# PowerControl.net
KiCad netlist of a schematic drawn in Altium Designer
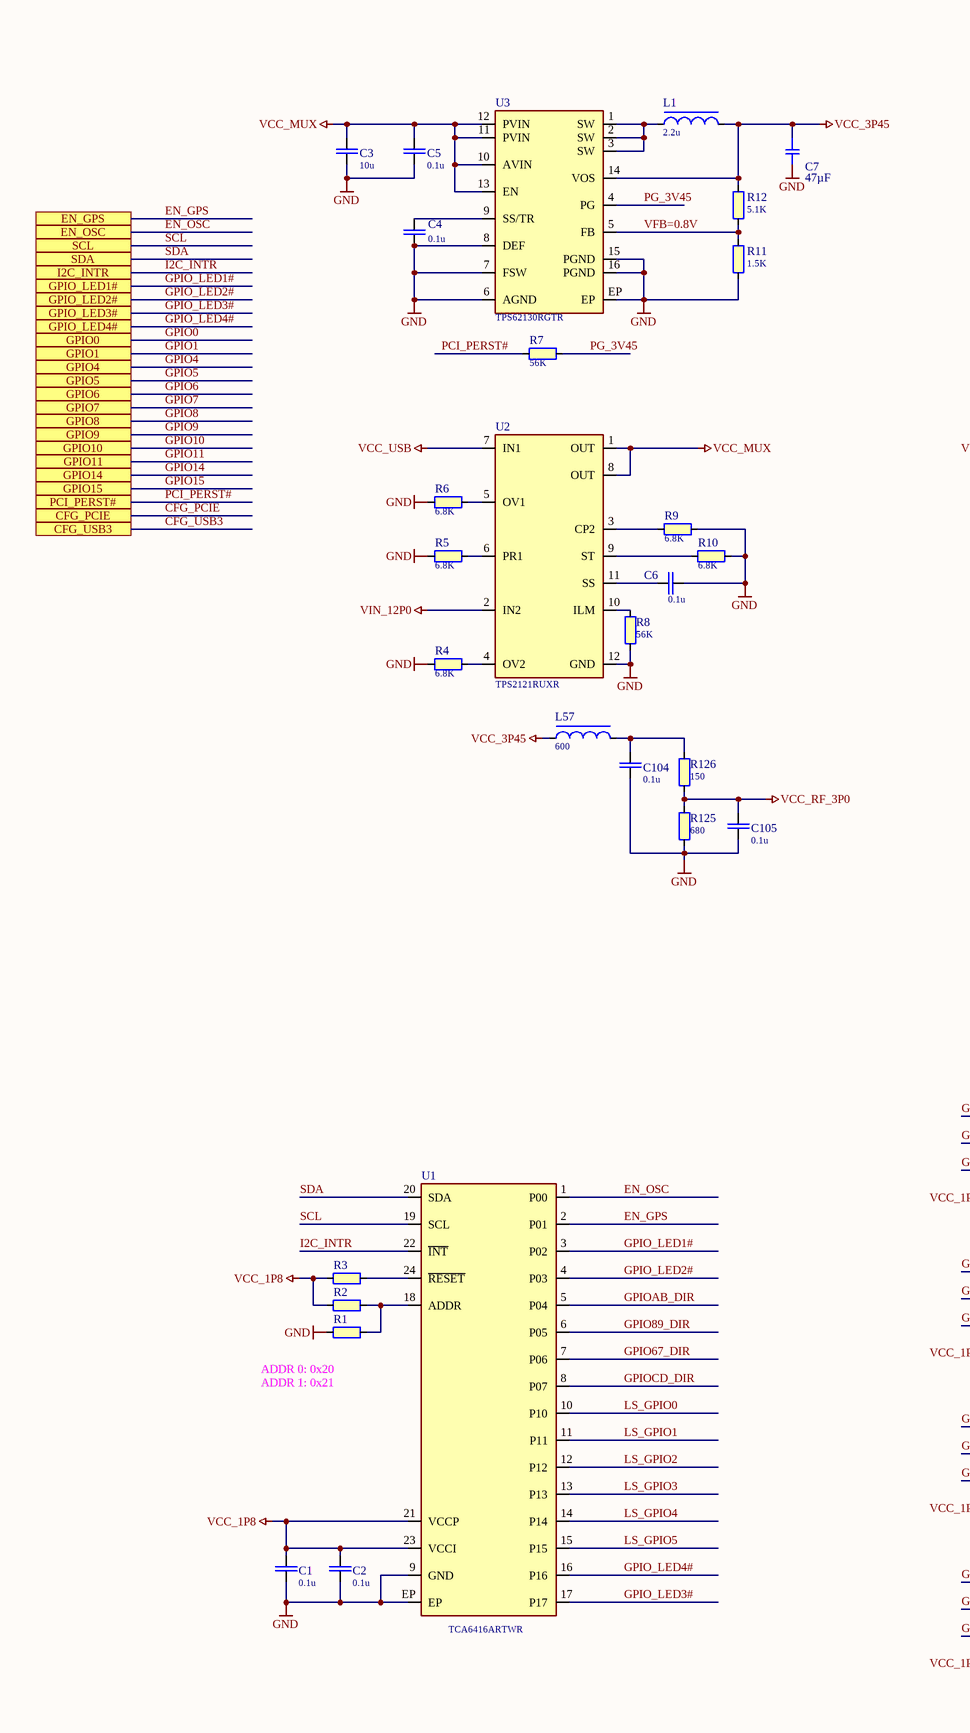
[diagram p0: PowerControl.SchDoc, left]
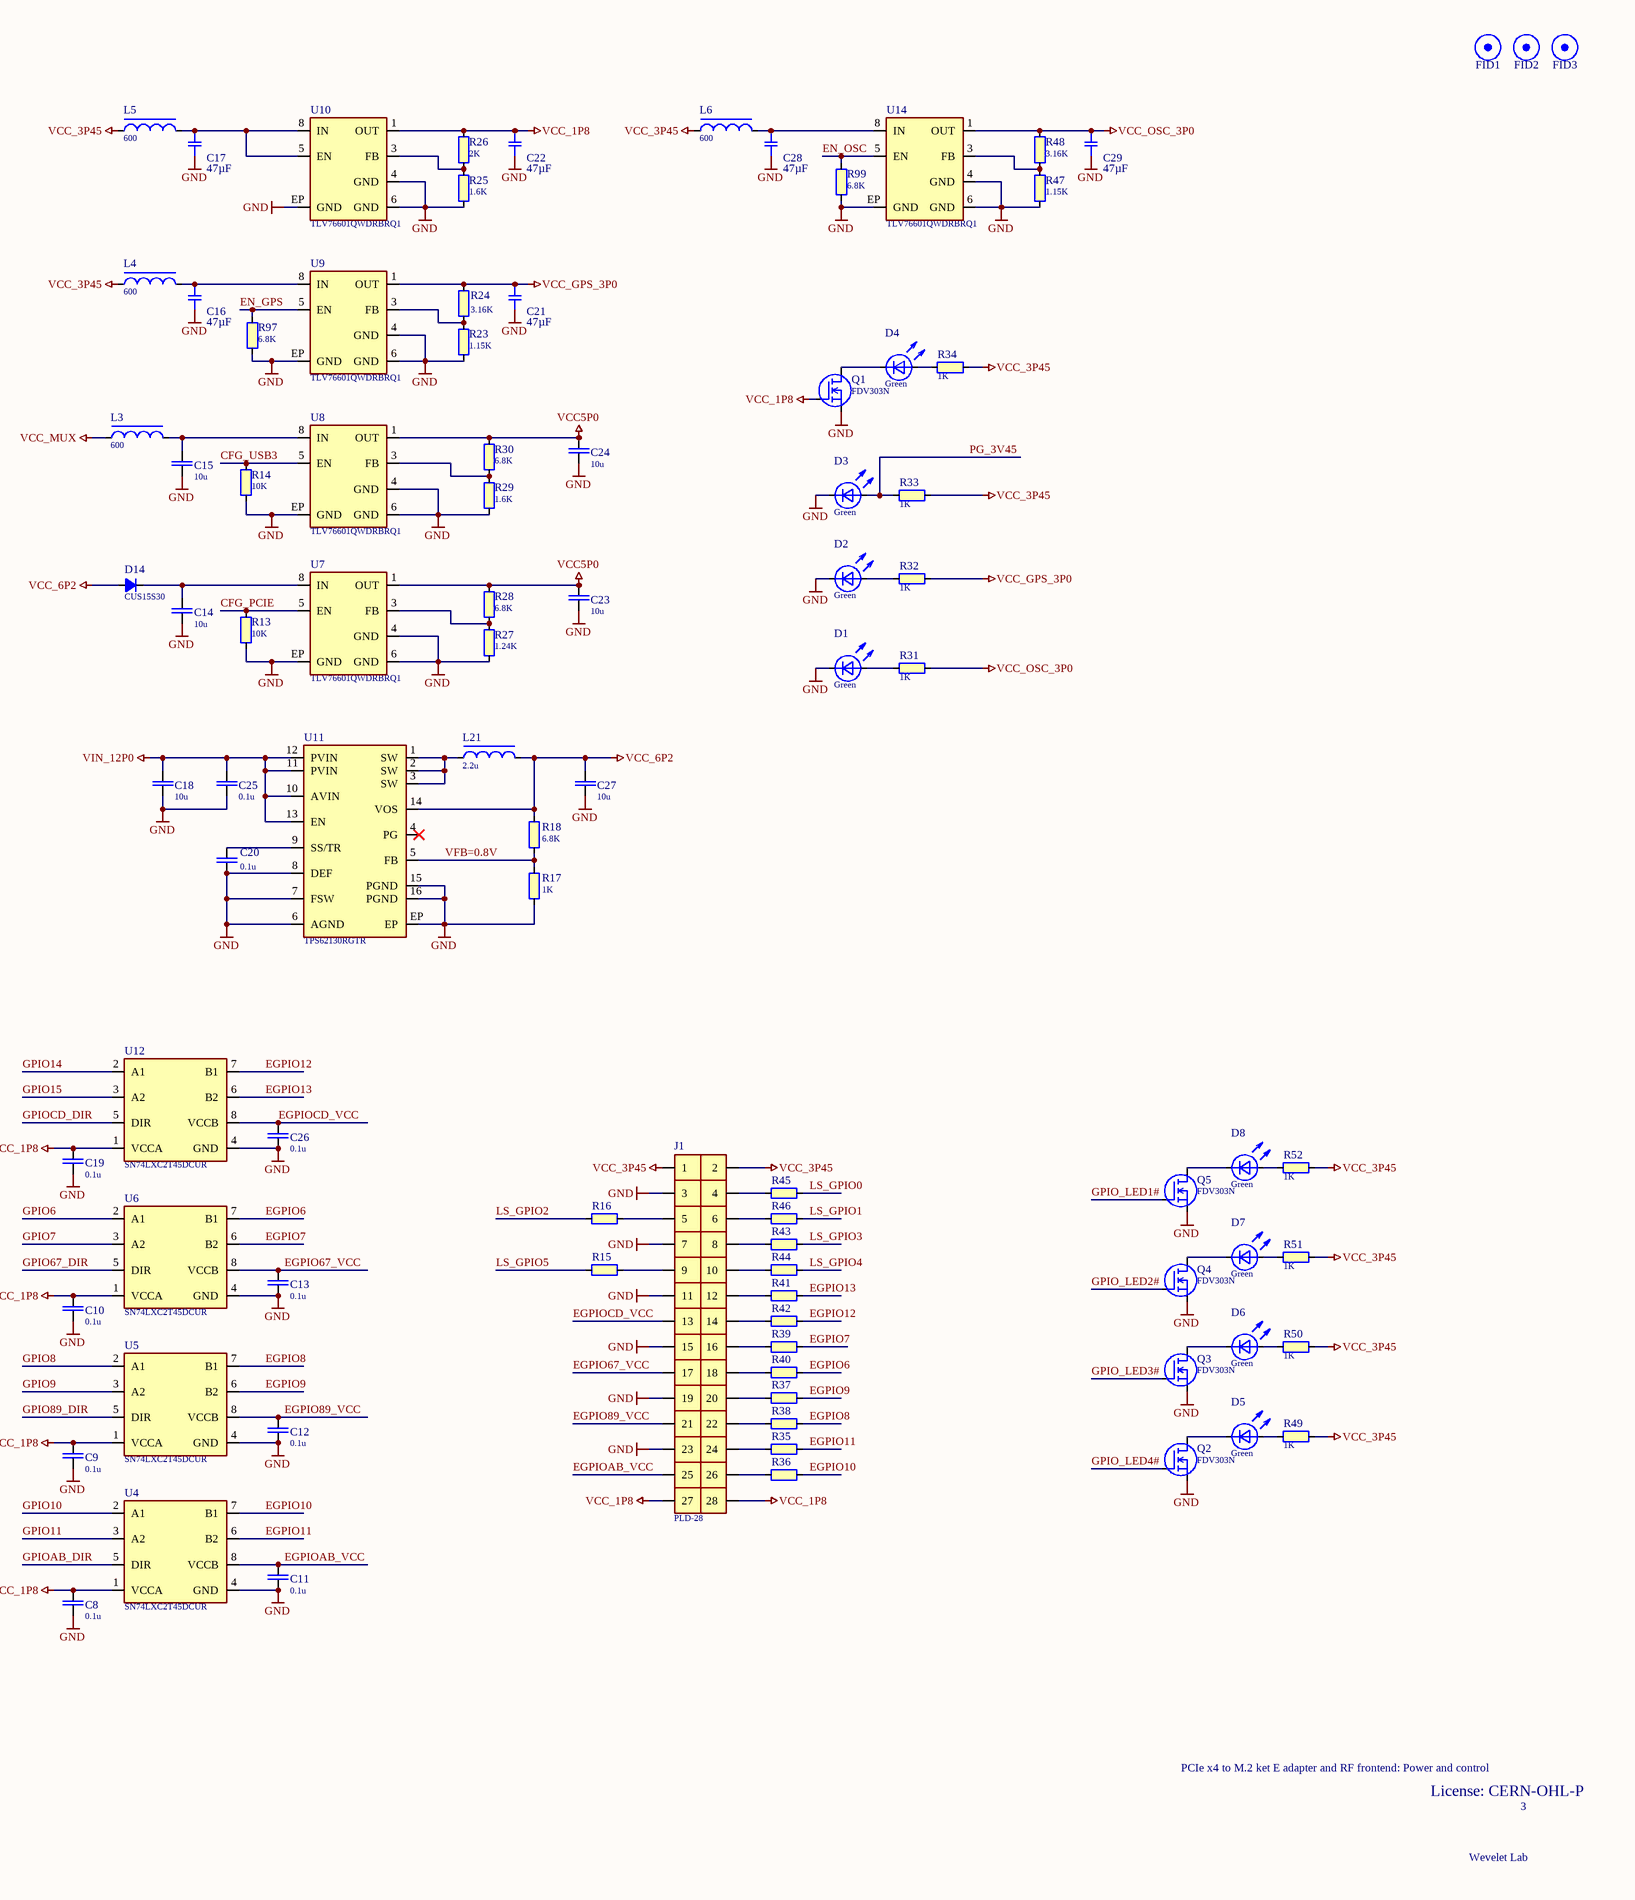
[diagram p1: PowerControl.SchDoc, right]

(export (version "E")
  (design (tool "Eeschema 10.0.6"))
  (components
    (comp (ref "C1")
      (value "0.1u")
      (footprint "CAPC100X50X55L25N")
      (description "Capacitor, 0.1u, 25V, 10%, X7R, 0402")
      (fields
        (field (name "MANUFACTURER") "Murata Electronics")
        (field (name "Comment") "GRM155R71E104KE14D")
      )
      (libsource (lib "Capacitors") (part "GRM155R71E104KE14D"))
    )
    (comp (ref "C2")
      (value "0.1u")
      (footprint "CAPC100X50X55L25N")
      (description "Capacitor, 0.1u, 25V, 10%, X7R, 0402")
      (fields
        (field (name "MANUFACTURER") "Murata Electronics")
        (field (name "Comment") "GRM155R71E104KE14D")
      )
      (libsource (lib "Capacitors") (part "GRM155R71E104KE14D"))
    )
    (comp (ref "C3")
      (value "10u")
      (footprint "CAPC160X80X100L40N")
      (description "Capacitor, 10u, 25V, 20%, X5R, 0603")
      (fields (field (name "Comment") "Cap-0603-X5R-25V-10u-20%"))
      (libsource (lib "Capacitors") (part "Cap-0603-X5R-25V-10u-20%"))
    )
    (comp (ref "C4")
      (value "0.1u")
      (footprint "CAPC100X50X55L25N")
      (description "Capacitor, 0.1u, 25V, 10%, X7R, 0402")
      (fields
        (field (name "MANUFACTURER") "Murata Electronics")
        (field (name "Comment") "GRM155R71E104KE14D")
      )
      (libsource (lib "Capacitors") (part "GRM155R71E104KE14D"))
    )
    (comp (ref "C5")
      (value "0.1u")
      (footprint "CAPC100X50X55L25N")
      (description "Capacitor, 0.1u, 25V, 10%, X7R, 0402")
      (fields
        (field (name "MANUFACTURER") "Murata Electronics")
        (field (name "Comment") "GRM155R71E104KE14D")
      )
      (libsource (lib "Capacitors") (part "GRM155R71E104KE14D"))
    )
    (comp (ref "C6")
      (value "0.1u")
      (footprint "CAPC100X50X55L25N")
      (description "Capacitor, 0.1u, 25V, 10%, X7R, 0402")
      (fields
        (field (name "MANUFACTURER") "Murata Electronics")
        (field (name "Comment") "GRM155R71E104KE14D")
      )
      (libsource (lib "Capacitors") (part "GRM155R71E104KE14D"))
    )
    (comp (ref "C7")
      (value "47µF")
      (footprint "SMD-0603-CAP_HighDensity")
      (description "CAP CER 47UF 4V X6S 0603")
      (fields
        (field (name "MANUFACTURER") "Murata Electronics North America")
        (field (name "DIGI-KEY PART NUMBER") "490-13246-2-ND")
      )
      (libsource (lib "Capacitors") (part "GRM188C80G476ME01D"))
    )
    (comp (ref "C8")
      (value "0.1u")
      (footprint "CAPC100X50X55L25N")
      (description "Capacitor, 0.1u, 25V, 10%, X7R, 0402")
      (fields
        (field (name "MANUFACTURER") "Murata Electronics")
        (field (name "Comment") "GRM155R71E104KE14D")
      )
      (libsource (lib "Capacitors") (part "GRM155R71E104KE14D"))
    )
    (comp (ref "C9")
      (value "0.1u")
      (footprint "CAPC100X50X55L25N")
      (description "Capacitor, 0.1u, 25V, 10%, X7R, 0402")
      (fields
        (field (name "MANUFACTURER") "Murata Electronics")
        (field (name "Comment") "GRM155R71E104KE14D")
      )
      (libsource (lib "Capacitors") (part "GRM155R71E104KE14D"))
    )
    (comp (ref "C10")
      (value "0.1u")
      (footprint "CAPC100X50X55L25N")
      (description "Capacitor, 0.1u, 25V, 10%, X7R, 0402")
      (fields
        (field (name "MANUFACTURER") "Murata Electronics")
        (field (name "Comment") "GRM155R71E104KE14D")
      )
      (libsource (lib "Capacitors") (part "GRM155R71E104KE14D"))
    )
    (comp (ref "C11")
      (value "0.1u")
      (footprint "CAPC100X50X55L25N")
      (description "Capacitor, 0.1u, 25V, 10%, X7R, 0402")
      (fields
        (field (name "MANUFACTURER") "Murata Electronics")
        (field (name "Comment") "GRM155R71E104KE14D")
      )
      (libsource (lib "Capacitors") (part "GRM155R71E104KE14D"))
    )
    (comp (ref "C12")
      (value "0.1u")
      (footprint "CAPC100X50X55L25N")
      (description "Capacitor, 0.1u, 25V, 10%, X7R, 0402")
      (fields
        (field (name "MANUFACTURER") "Murata Electronics")
        (field (name "Comment") "GRM155R71E104KE14D")
      )
      (libsource (lib "Capacitors") (part "GRM155R71E104KE14D"))
    )
    (comp (ref "C13")
      (value "0.1u")
      (footprint "CAPC100X50X55L25N")
      (description "Capacitor, 0.1u, 25V, 10%, X7R, 0402")
      (fields
        (field (name "MANUFACTURER") "Murata Electronics")
        (field (name "Comment") "GRM155R71E104KE14D")
      )
      (libsource (lib "Capacitors") (part "GRM155R71E104KE14D"))
    )
    (comp (ref "C14")
      (value "10u")
      (footprint "CAPC160X80X100L40N")
      (description "Capacitor, 10u, 25V, 20%, X5R, 0603")
      (fields (field (name "Comment") "Cap-0603-X5R-25V-10u-20%"))
      (libsource (lib "Capacitors") (part "Cap-0603-X5R-25V-10u-20%"))
    )
    (comp (ref "C15")
      (value "10u")
      (footprint "CAPC160X80X100L40N")
      (description "Capacitor, 10u, 25V, 20%, X5R, 0603")
      (fields (field (name "Comment") "Cap-0603-X5R-25V-10u-20%"))
      (libsource (lib "Capacitors") (part "Cap-0603-X5R-25V-10u-20%"))
    )
    (comp (ref "C16")
      (value "47µF")
      (footprint "SMD-0603-CAP_HighDensity")
      (description "CAP CER 47UF 4V X6S 0603")
      (fields
        (field (name "MANUFACTURER") "Murata Electronics North America")
        (field (name "DIGI-KEY PART NUMBER") "490-13246-2-ND")
      )
      (libsource (lib "Capacitors") (part "GRM188C80G476ME01D"))
    )
    (comp (ref "C17")
      (value "47µF")
      (footprint "SMD-0603-CAP_HighDensity")
      (description "CAP CER 47UF 4V X6S 0603")
      (fields
        (field (name "MANUFACTURER") "Murata Electronics North America")
        (field (name "DIGI-KEY PART NUMBER") "490-13246-2-ND")
      )
      (libsource (lib "Capacitors") (part "GRM188C80G476ME01D"))
    )
    (comp (ref "C18")
      (value "10u")
      (footprint "CAPC160X80X100L40N")
      (description "Capacitor, 10u, 25V, 20%, X5R, 0603")
      (fields (field (name "Comment") "Cap-0603-X5R-25V-10u-20%"))
      (libsource (lib "Capacitors") (part "Cap-0603-X5R-25V-10u-20%"))
    )
    (comp (ref "C19")
      (value "0.1u")
      (footprint "CAPC100X50X55L25N")
      (description "Capacitor, 0.1u, 25V, 10%, X7R, 0402")
      (fields
        (field (name "MANUFACTURER") "Murata Electronics")
        (field (name "Comment") "GRM155R71E104KE14D")
      )
      (libsource (lib "Capacitors") (part "GRM155R71E104KE14D"))
    )
    (comp (ref "C20")
      (value "0.1u")
      (footprint "CAPC100X50X55L25N")
      (description "Capacitor, 0.1u, 25V, 10%, X7R, 0402")
      (fields
        (field (name "MANUFACTURER") "Murata Electronics")
        (field (name "Comment") "GRM155R71E104KE14D")
      )
      (libsource (lib "Capacitors") (part "GRM155R71E104KE14D"))
    )
    (comp (ref "C21")
      (value "47µF")
      (footprint "SMD-0603-CAP_HighDensity")
      (description "CAP CER 47UF 4V X6S 0603")
      (fields
        (field (name "MANUFACTURER") "Murata Electronics North America")
        (field (name "DIGI-KEY PART NUMBER") "490-13246-2-ND")
      )
      (libsource (lib "Capacitors") (part "GRM188C80G476ME01D"))
    )
    (comp (ref "C22")
      (value "47µF")
      (footprint "SMD-0603-CAP_HighDensity")
      (description "CAP CER 47UF 4V X6S 0603")
      (fields
        (field (name "MANUFACTURER") "Murata Electronics North America")
        (field (name "DIGI-KEY PART NUMBER") "490-13246-2-ND")
      )
      (libsource (lib "Capacitors") (part "GRM188C80G476ME01D"))
    )
    (comp (ref "C23")
      (value "10u")
      (footprint "CAPC160X80X100L40N")
      (description "Capacitor, 10u, 25V, 20%, X5R, 0603")
      (fields (field (name "Comment") "Cap-0603-X5R-25V-10u-20%"))
      (libsource (lib "Capacitors") (part "Cap-0603-X5R-25V-10u-20%"))
    )
    (comp (ref "C24")
      (value "10u")
      (footprint "CAPC160X80X100L40N")
      (description "Capacitor, 10u, 25V, 20%, X5R, 0603")
      (fields (field (name "Comment") "Cap-0603-X5R-25V-10u-20%"))
      (libsource (lib "Capacitors") (part "Cap-0603-X5R-25V-10u-20%"))
    )
    (comp (ref "C25")
      (value "0.1u")
      (footprint "CAPC100X50X55L25N")
      (description "Capacitor, 0.1u, 25V, 10%, X7R, 0402")
      (fields
        (field (name "MANUFACTURER") "Murata Electronics")
        (field (name "Comment") "GRM155R71E104KE14D")
      )
      (libsource (lib "Capacitors") (part "GRM155R71E104KE14D"))
    )
    (comp (ref "C26")
      (value "0.1u")
      (footprint "CAPC100X50X55L25N")
      (description "Capacitor, 0.1u, 25V, 10%, X7R, 0402")
      (fields
        (field (name "MANUFACTURER") "Murata Electronics")
        (field (name "Comment") "GRM155R71E104KE14D")
      )
      (libsource (lib "Capacitors") (part "GRM155R71E104KE14D"))
    )
    (comp (ref "C27")
      (value "10u")
      (footprint "CAPC160X80X100L40N")
      (description "Capacitor, 10u, 25V, 20%, X5R, 0603")
      (fields (field (name "Comment") "Cap-0603-X5R-25V-10u-20%"))
      (libsource (lib "Capacitors") (part "Cap-0603-X5R-25V-10u-20%"))
    )
    (comp (ref "C28")
      (value "47µF")
      (footprint "SMD-0603-CAP_HighDensity")
      (description "CAP CER 47UF 4V X6S 0603")
      (fields
        (field (name "MANUFACTURER") "Murata Electronics North America")
        (field (name "DIGI-KEY PART NUMBER") "490-13246-2-ND")
      )
      (libsource (lib "Capacitors") (part "GRM188C80G476ME01D"))
    )
    (comp (ref "C29")
      (value "47µF")
      (footprint "SMD-0603-CAP_HighDensity")
      (description "CAP CER 47UF 4V X6S 0603")
      (fields
        (field (name "MANUFACTURER") "Murata Electronics North America")
        (field (name "DIGI-KEY PART NUMBER") "490-13246-2-ND")
      )
      (libsource (lib "Capacitors") (part "GRM188C80G476ME01D"))
    )
    (comp (ref "C104")
      (value "0.1u")
      (footprint "CAPC100X50X55L25N")
      (description "Capacitor, 0.1u, 25V, 10%, X7R, 0402")
      (fields
        (field (name "MANUFACTURER") "Murata Electronics")
        (field (name "Comment") "GRM155R71E104KE14D")
      )
      (libsource (lib "Capacitors") (part "GRM155R71E104KE14D"))
    )
    (comp (ref "C105")
      (value "0.1u")
      (footprint "CAPC100X50X55L25N")
      (description "Capacitor, 0.1u, 25V, 10%, X7R, 0402")
      (fields
        (field (name "MANUFACTURER") "Murata Electronics")
        (field (name "Comment") "GRM155R71E104KE14D")
      )
      (libsource (lib "Capacitors") (part "GRM155R71E104KE14D"))
    )
    (comp (ref "D1")
      (value "Green")
      (footprint "LEDC160X80X80L40N-Green")
      (description "LED Diode, Green, -30/+85, SMD0603")
      (fields (field (name "MANUFACTURER") "Lite-On Inc.") (field (name "Comment") "LTST-C190KGKT"))
      (libsource (lib "Diode_Transistor") (part "LTST-C190KGKT"))
    )
    (comp (ref "D2")
      (value "Green")
      (footprint "LEDC160X80X80L40N-Green")
      (description "LED Diode, Green, -30/+85, SMD0603")
      (fields (field (name "MANUFACTURER") "Lite-On Inc.") (field (name "Comment") "LTST-C190KGKT"))
      (libsource (lib "Diode_Transistor") (part "LTST-C190KGKT"))
    )
    (comp (ref "D3")
      (value "Green")
      (footprint "LEDC160X80X80L40N-Green")
      (description "LED Diode, Green, -30/+85, SMD0603")
      (fields (field (name "MANUFACTURER") "Lite-On Inc.") (field (name "Comment") "LTST-C190KGKT"))
      (libsource (lib "Diode_Transistor") (part "LTST-C190KGKT"))
    )
    (comp (ref "D4")
      (value "Green")
      (footprint "LEDC160X80X80L40N-Green")
      (description "LED Diode, Green, -30/+85, SMD0603")
      (fields (field (name "MANUFACTURER") "Lite-On Inc.") (field (name "Comment") "LTST-C190KGKT"))
      (libsource (lib "Diode_Transistor") (part "LTST-C190KGKT"))
    )
    (comp (ref "D5")
      (value "Green")
      (footprint "LEDC160X80X80L40N-Green")
      (description "LED Diode, Green, -30/+85, SMD0603")
      (fields (field (name "MANUFACTURER") "Lite-On Inc.") (field (name "Comment") "LTST-C190KGKT"))
      (libsource (lib "Diode_Transistor") (part "LTST-C190KGKT"))
    )
    (comp (ref "D6")
      (value "Green")
      (footprint "LEDC160X80X80L40N-Green")
      (description "LED Diode, Green, -30/+85, SMD0603")
      (fields (field (name "MANUFACTURER") "Lite-On Inc.") (field (name "Comment") "LTST-C190KGKT"))
      (libsource (lib "Diode_Transistor") (part "LTST-C190KGKT"))
    )
    (comp (ref "D7")
      (value "Green")
      (footprint "LEDC160X80X80L40N-Green")
      (description "LED Diode, Green, -30/+85, SMD0603")
      (fields (field (name "MANUFACTURER") "Lite-On Inc.") (field (name "Comment") "LTST-C190KGKT"))
      (libsource (lib "Diode_Transistor") (part "LTST-C190KGKT"))
    )
    (comp (ref "D8")
      (value "Green")
      (footprint "LEDC160X80X80L40N-Green")
      (description "LED Diode, Green, -30/+85, SMD0603")
      (fields (field (name "MANUFACTURER") "Lite-On Inc.") (field (name "Comment") "LTST-C190KGKT"))
      (libsource (lib "Diode_Transistor") (part "LTST-C190KGKT"))
    )
    (comp (ref "D14")
      (value "CUS15S30")
      (footprint "INDC100X60X60L30N")
      (description "Diode, Schottky, 20V, 1.5A, 0.3Vf, -50/+125, SOD-323-2")
      (fields (field (name "MANUFACTURER") "Toshiba") (field (name "Comment") "CUS15S30,H3F"))
      (libsource (lib "Diode_Transistor") (part "CUS15S30"))
    )
    (comp (ref "FID1")
      (value "Fiducial")
      (footprint "Fiducial_3D")
      (libsource (lib "Mech") (part "Fiducial"))
    )
    (comp (ref "FID2")
      (value "Fiducial")
      (footprint "Fiducial_3D")
      (libsource (lib "Mech") (part "Fiducial"))
    )
    (comp (ref "FID3")
      (value "Fiducial")
      (footprint "Fiducial_3D")
      (libsource (lib "Mech") (part "Fiducial"))
    )
    (comp (ref "J1")
      (value "PLD-28")
      (footprint "PLD-28")
      (description "Conn, Header 12x2, 2.54mm, Trough Hole")
      (libsource (lib "Connectors") (part "PLD-28"))
    )
    (comp (ref "L1")
      (value "2.2u")
      (footprint "IND_TAIYO_NRS5020")
      (description "Inductor, 2.2u, 2,9A, 42mOhm, +/-30%, -25/+125, SMD")
      (fields (field (name "MANUFACTURER") "Taiyo Yuden") (field (name "Comment") "NRS5020T2R2NMGJ"))
      (libsource (lib "Inductor_Transformer") (part "NRS5020T2R2NMGJ"))
    )
    (comp (ref "L3")
      (value "600")
      (footprint "INDC100X60X60L30N")
      (description "Ferrite bead, 600Ohm@100MHz, 0,3A, 700mOhm, -55/+125, SMD0402")
      (fields (field (name "MANUFACTURER") "Murata Electronics") (field (name "Comment") "BLM15HG601SN1D"))
      (libsource (lib "Inductor_Transformer") (part "BLM15HG601SN1D"))
    )
    (comp (ref "L4")
      (value "600")
      (footprint "INDC100X60X60L30N")
      (description "Ferrite bead, 600Ohm@100MHz, 0,3A, 700mOhm, -55/+125, SMD0402")
      (fields (field (name "MANUFACTURER") "Murata Electronics") (field (name "Comment") "BLM15HG601SN1D"))
      (libsource (lib "Inductor_Transformer") (part "BLM15HG601SN1D"))
    )
    (comp (ref "L5")
      (value "600")
      (footprint "INDC100X60X60L30N")
      (description "Ferrite bead, 600Ohm@100MHz, 0,3A, 700mOhm, -55/+125, SMD0402")
      (fields (field (name "MANUFACTURER") "Murata Electronics") (field (name "Comment") "BLM15HG601SN1D"))
      (libsource (lib "Inductor_Transformer") (part "BLM15HG601SN1D"))
    )
    (comp (ref "L6")
      (value "600")
      (footprint "INDC100X60X60L30N")
      (description "Ferrite bead, 600Ohm@100MHz, 0,3A, 700mOhm, -55/+125, SMD0402")
      (fields (field (name "MANUFACTURER") "Murata Electronics") (field (name "Comment") "BLM15HG601SN1D"))
      (libsource (lib "Inductor_Transformer") (part "BLM15HG601SN1D"))
    )
    (comp (ref "L21")
      (value "2.2u")
      (footprint "IND_TAIYO_NRS5020")
      (description "Inductor, 2.2u, 2,9A, 42mOhm, +/-30%, -25/+125, SMD")
      (fields (field (name "MANUFACTURER") "Taiyo Yuden") (field (name "Comment") "NRS5020T2R2NMGJ"))
      (libsource (lib "Inductor_Transformer") (part "NRS5020T2R2NMGJ"))
    )
    (comp (ref "L57")
      (value "600")
      (footprint "INDC100X60X60L30N")
      (description "Ferrite bead, 600Ohm@100MHz, 0,3A, 700mOhm, -55/+125, SMD0402")
      (fields (field (name "MANUFACTURER") "Murata Electronics") (field (name "Comment") "BLM15HG601SN1D"))
      (libsource (lib "Inductor_Transformer") (part "BLM15HG601SN1D"))
    )
    (comp (ref "Q1")
      (value "FDV303N")
      (footprint "SOT23-3P95_245X110L45X44N")
      (description "Transistor, MOSFET, N-CH, 25V, 0.68A, -55/+150, SOT-23")
      (fields (field (name "MANUFACTURER") "Onsemi"))
      (libsource (lib "Diode_Transistor") (part "FDV303N"))
    )
    (comp (ref "Q2")
      (value "FDV303N")
      (footprint "SOT23-3P95_245X110L45X44N")
      (description "Transistor, MOSFET, N-CH, 25V, 0.68A, -55/+150, SOT-23")
      (fields (field (name "MANUFACTURER") "Onsemi"))
      (libsource (lib "Diode_Transistor") (part "FDV303N"))
    )
    (comp (ref "Q3")
      (value "FDV303N")
      (footprint "SOT23-3P95_245X110L45X44N")
      (description "Transistor, MOSFET, N-CH, 25V, 0.68A, -55/+150, SOT-23")
      (fields (field (name "MANUFACTURER") "Onsemi"))
      (libsource (lib "Diode_Transistor") (part "FDV303N"))
    )
    (comp (ref "Q4")
      (value "FDV303N")
      (footprint "SOT23-3P95_245X110L45X44N")
      (description "Transistor, MOSFET, N-CH, 25V, 0.68A, -55/+150, SOT-23")
      (fields (field (name "MANUFACTURER") "Onsemi"))
      (libsource (lib "Diode_Transistor") (part "FDV303N"))
    )
    (comp (ref "Q5")
      (value "FDV303N")
      (footprint "SOT23-3P95_245X110L45X44N")
      (description "Transistor, MOSFET, N-CH, 25V, 0.68A, -55/+150, SOT-23")
      (fields (field (name "MANUFACTURER") "Onsemi"))
      (libsource (lib "Diode_Transistor") (part "FDV303N"))
    )
    (comp (ref "R1")
      (value "DNP")
      (footprint "RESC100X50X40L20N")
      (description "Resistor, DNP, 0.063W, 5%, 0402")
      (fields (field (name "Comment") "Res-0402-DNP"))
      (libsource (lib "Resistors") (part "Res-0402-DNP"))
    )
    (comp (ref "R2")
      (value "33")
      (footprint "RESC100X50X40L20N")
      (description "Resistor, 33, 0.063W, 5%, 0402")
      (fields (field (name "Comment") "RC0402FR-0733RL"))
      (libsource (lib "Resistors") (part "Res-0402-33-5%"))
    )
    (comp (ref "R3")
      (value "6.8K")
      (footprint "RESC100X50X40L20N")
      (description "Resistor, 6.8K, 0.063W, 1%, 0402")
      (fields (field (name "Comment") "RC0402FR-076K8L"))
      (libsource (lib "Resistors") (part "Res-0402-6.8K-1%"))
    )
    (comp (ref "R4")
      (value "6.8K")
      (footprint "RESC100X50X40L20N")
      (description "Resistor, 6.8K, 0.063W, 1%, 0402")
      (fields (field (name "Comment") "RC0402FR-076K8L"))
      (libsource (lib "Resistors") (part "Res-0402-6.8K-1%"))
    )
    (comp (ref "R5")
      (value "6.8K")
      (footprint "RESC100X50X40L20N")
      (description "Resistor, 6.8K, 0.063W, 1%, 0402")
      (fields (field (name "Comment") "RC0402FR-076K8L"))
      (libsource (lib "Resistors") (part "Res-0402-6.8K-1%"))
    )
    (comp (ref "R6")
      (value "6.8K")
      (footprint "RESC100X50X40L20N")
      (description "Resistor, 6.8K, 0.063W, 1%, 0402")
      (fields (field (name "Comment") "RC0402FR-076K8L"))
      (libsource (lib "Resistors") (part "Res-0402-6.8K-1%"))
    )
    (comp (ref "R7")
      (value "56K")
      (footprint "RESC100X50X40L20N")
      (description "Resistor, 56K, 0.063W, 5%, 0402")
      (fields (field (name "Comment") "RC0402FR-0756KL"))
      (libsource (lib "Resistors") (part "Res-0402-56K-5%"))
    )
    (comp (ref "R8")
      (value "56K")
      (footprint "RESC100X50X40L20N")
      (description "Resistor, 56K, 0.063W, 5%, 0402")
      (fields (field (name "Comment") "RC0402FR-0756KL"))
      (libsource (lib "") (part "Res-0402-56K-5%_1"))
    )
    (comp (ref "R9")
      (value "6.8K")
      (footprint "RESC100X50X40L20N")
      (description "Resistor, 6.8K, 0.063W, 1%, 0402")
      (fields (field (name "Comment") "RC0402FR-076K8L"))
      (libsource (lib "Resistors") (part "Res-0402-6.8K-1%"))
    )
    (comp (ref "R10")
      (value "6.8K")
      (footprint "RESC100X50X40L20N")
      (description "Resistor, 6.8K, 0.063W, 1%, 0402")
      (fields (field (name "Comment") "RC0402FR-076K8L"))
      (libsource (lib "Resistors") (part "Res-0402-6.8K-1%"))
    )
    (comp (ref "R11")
      (value "1.5K")
      (footprint "RESC100X50X40L20N")
      (description "Resistor, 1.5K, 0.063W, 1%, 0402")
      (fields (field (name "Comment") "RC0402FR-071K5L"))
      (libsource (lib "Resistors") (part "Res-0402-1.5K-1%"))
    )
    (comp (ref "R12")
      (value "5.1K")
      (footprint "RESC100X50X40L20N")
      (description "Resistor, 5.1K, 0.063W, 1%, 0402")
      (fields (field (name "Comment") "RC0402FR-075K1L"))
      (libsource (lib "Resistors") (part "Res-0402-5.1K-1%"))
    )
    (comp (ref "R13")
      (value "10K")
      (footprint "RESC100X50X40L20N")
      (description "Resistor, 10K, 0.063W, 5%, 0402")
      (fields (field (name "Comment") "RC0402FR-0710KL"))
      (libsource (lib "Resistors") (part "Res-0402-10K-5%"))
    )
    (comp (ref "R14")
      (value "10K")
      (footprint "RESC100X50X40L20N")
      (description "Resistor, 10K, 0.063W, 5%, 0402")
      (fields (field (name "Comment") "RC0402FR-0710KL"))
      (libsource (lib "Resistors") (part "Res-0402-10K-5%"))
    )
    (comp (ref "R15")
      (value "33")
      (footprint "RESC100X50X40L20N")
      (description "Resistor, 33, 0.063W, 5%, 0402")
      (fields (field (name "Comment") "RC0402FR-0733RL"))
      (libsource (lib "Resistors") (part "Res-0402-33-5%"))
    )
    (comp (ref "R16")
      (value "33")
      (footprint "RESC100X50X40L20N")
      (description "Resistor, 33, 0.063W, 5%, 0402")
      (fields (field (name "Comment") "RC0402FR-0733RL"))
      (libsource (lib "Resistors") (part "Res-0402-33-5%"))
    )
    (comp (ref "R17")
      (value "1K")
      (footprint "RESC100X50X40L20N")
      (description "Resistor, 1K, 0.063W, 5%, 0402")
      (fields (field (name "Comment") "RC0402FR-071KL"))
      (libsource (lib "") (part "Res-0402-1K-5%_1"))
    )
    (comp (ref "R18")
      (value "6.8K")
      (footprint "RESC100X50X40L20N")
      (description "Resistor, 6.8K, 0.063W, 1%, 0402")
      (fields (field (name "Comment") "RC0402FR-076K8L"))
      (libsource (lib "") (part "Res-0402-6.8K-1%_1"))
    )
    (comp (ref "R23")
      (value "1.15K")
      (footprint "RESC100X50X40L20N")
      (description "Resistor, 1.15K, 0.063W, 1%, 0402")
      (fields (field (name "Comment") "RC0402FR-071K15L"))
      (libsource (lib "Resistors") (part "Res-0402-1.15K-1%"))
    )
    (comp (ref "R24")
      (value "3.16K")
      (footprint "RESC100X50X40L20N")
      (description "Resistor, 3.16K, 0.063W, 1%, 0402")
      (fields (field (name "Comment") "RC0402FR-073K16L"))
      (libsource (lib "Resistors") (part "Res-0402-3.16K-1%"))
    )
    (comp (ref "R25")
      (value "1.6K")
      (footprint "RESC100X50X40L20N")
      (description "Resistor, 1.6K, 0.063W, 1%, 0402")
      (fields (field (name "Comment") "RC0402FR-071K6L"))
      (libsource (lib "Resistors") (part "Res-0402-1.6K-1%"))
    )
    (comp (ref "R26")
      (value "2K")
      (footprint "RESC100X50X40L20N")
      (description "Resistor, 2K, 0.063W, 1%, 0402")
      (fields (field (name "Comment") "RC0402FR-072KL"))
      (libsource (lib "Resistors") (part "Res-0402-2K-1%"))
    )
    (comp (ref "R27")
      (value "1.24K")
      (footprint "RESC100X50X40L20N")
      (description "Resistor, 1.24K, 0.063W, 1%, 0402")
      (fields (field (name "Comment") "RC0402FR-071K24L"))
      (libsource (lib "Resistors") (part "Res-0402-1.24K-1%"))
    )
    (comp (ref "R28")
      (value "6.8K")
      (footprint "RESC100X50X40L20N")
      (description "Resistor, 6.8K, 0.063W, 1%, 0402")
      (fields (field (name "Comment") "RC0402FR-076K8L"))
      (libsource (lib "") (part "Res-0402-6.8K-1%_1"))
    )
    (comp (ref "R29")
      (value "1.6K")
      (footprint "RESC100X50X40L20N")
      (description "Resistor, 1.6K, 0.063W, 1%, 0402")
      (fields (field (name "Comment") "RC0402FR-071K6L"))
      (libsource (lib "Resistors") (part "Res-0402-1.6K-1%"))
    )
    (comp (ref "R30")
      (value "6.8K")
      (footprint "RESC100X50X40L20N")
      (description "Resistor, 6.8K, 0.063W, 1%, 0402")
      (fields (field (name "Comment") "RC0402FR-076K8L"))
      (libsource (lib "") (part "Res-0402-6.8K-1%_1"))
    )
    (comp (ref "R31")
      (value "1K")
      (footprint "RESC100X50X40L20N")
      (description "Resistor, 1K, 0.063W, 5%, 0402")
      (fields (field (name "Comment") "RC0402FR-071KL"))
      (libsource (lib "Resistors") (part "Res-0402-1K-5%"))
    )
    (comp (ref "R32")
      (value "1K")
      (footprint "RESC100X50X40L20N")
      (description "Resistor, 1K, 0.063W, 5%, 0402")
      (fields (field (name "Comment") "RC0402FR-071KL"))
      (libsource (lib "Resistors") (part "Res-0402-1K-5%"))
    )
    (comp (ref "R33")
      (value "1K")
      (footprint "RESC100X50X40L20N")
      (description "Resistor, 1K, 0.063W, 5%, 0402")
      (fields (field (name "Comment") "RC0402FR-071KL"))
      (libsource (lib "Resistors") (part "Res-0402-1K-5%"))
    )
    (comp (ref "R34")
      (value "1K")
      (footprint "RESC100X50X40L20N")
      (description "Resistor, 1K, 0.063W, 5%, 0402")
      (fields (field (name "Comment") "RC0402FR-071KL"))
      (libsource (lib "Resistors") (part "Res-0402-1K-5%"))
    )
    (comp (ref "R35")
      (value "33")
      (footprint "RESC100X50X40L20N")
      (description "Resistor, 33, 0.063W, 5%, 0402")
      (fields (field (name "Comment") "RC0402FR-0733RL"))
      (libsource (lib "Resistors") (part "Res-0402-33-5%"))
    )
    (comp (ref "R36")
      (value "33")
      (footprint "RESC100X50X40L20N")
      (description "Resistor, 33, 0.063W, 5%, 0402")
      (fields (field (name "Comment") "RC0402FR-0733RL"))
      (libsource (lib "Resistors") (part "Res-0402-33-5%"))
    )
    (comp (ref "R37")
      (value "33")
      (footprint "RESC100X50X40L20N")
      (description "Resistor, 33, 0.063W, 5%, 0402")
      (fields (field (name "Comment") "RC0402FR-0733RL"))
      (libsource (lib "Resistors") (part "Res-0402-33-5%"))
    )
    (comp (ref "R38")
      (value "33")
      (footprint "RESC100X50X40L20N")
      (description "Resistor, 33, 0.063W, 5%, 0402")
      (fields (field (name "Comment") "RC0402FR-0733RL"))
      (libsource (lib "Resistors") (part "Res-0402-33-5%"))
    )
    (comp (ref "R39")
      (value "33")
      (footprint "RESC100X50X40L20N")
      (description "Resistor, 33, 0.063W, 5%, 0402")
      (fields (field (name "Comment") "RC0402FR-0733RL"))
      (libsource (lib "Resistors") (part "Res-0402-33-5%"))
    )
    (comp (ref "R40")
      (value "33")
      (footprint "RESC100X50X40L20N")
      (description "Resistor, 33, 0.063W, 5%, 0402")
      (fields (field (name "Comment") "RC0402FR-0733RL"))
      (libsource (lib "Resistors") (part "Res-0402-33-5%"))
    )
    (comp (ref "R41")
      (value "33")
      (footprint "RESC100X50X40L20N")
      (description "Resistor, 33, 0.063W, 5%, 0402")
      (fields (field (name "Comment") "RC0402FR-0733RL"))
      (libsource (lib "Resistors") (part "Res-0402-33-5%"))
    )
    (comp (ref "R42")
      (value "33")
      (footprint "RESC100X50X40L20N")
      (description "Resistor, 33, 0.063W, 5%, 0402")
      (fields (field (name "Comment") "RC0402FR-0733RL"))
      (libsource (lib "Resistors") (part "Res-0402-33-5%"))
    )
    (comp (ref "R43")
      (value "33")
      (footprint "RESC100X50X40L20N")
      (description "Resistor, 33, 0.063W, 5%, 0402")
      (fields (field (name "Comment") "RC0402FR-0733RL"))
      (libsource (lib "Resistors") (part "Res-0402-33-5%"))
    )
    (comp (ref "R44")
      (value "33")
      (footprint "RESC100X50X40L20N")
      (description "Resistor, 33, 0.063W, 5%, 0402")
      (fields (field (name "Comment") "RC0402FR-0733RL"))
      (libsource (lib "Resistors") (part "Res-0402-33-5%"))
    )
    (comp (ref "R45")
      (value "33")
      (footprint "RESC100X50X40L20N")
      (description "Resistor, 33, 0.063W, 5%, 0402")
      (fields (field (name "Comment") "RC0402FR-0733RL"))
      (libsource (lib "Resistors") (part "Res-0402-33-5%"))
    )
    (comp (ref "R46")
      (value "33")
      (footprint "RESC100X50X40L20N")
      (description "Resistor, 33, 0.063W, 5%, 0402")
      (fields (field (name "Comment") "RC0402FR-0733RL"))
      (libsource (lib "Resistors") (part "Res-0402-33-5%"))
    )
    (comp (ref "R47")
      (value "1.15K")
      (footprint "RESC100X50X40L20N")
      (description "Resistor, 1.15K, 0.063W, 1%, 0402")
      (fields (field (name "Comment") "RC0402FR-071K15L"))
      (libsource (lib "Resistors") (part "Res-0402-1.15K-1%"))
    )
    (comp (ref "R48")
      (value "3.16K")
      (footprint "RESC100X50X40L20N")
      (description "Resistor, 3.16K, 0.063W, 1%, 0402")
      (fields (field (name "Comment") "RC0402FR-073K16L"))
      (libsource (lib "Resistors") (part "Res-0402-3.16K-1%"))
    )
    (comp (ref "R49")
      (value "1K")
      (footprint "RESC100X50X40L20N")
      (description "Resistor, 1K, 0.063W, 5%, 0402")
      (fields (field (name "Comment") "RC0402FR-071KL"))
      (libsource (lib "Resistors") (part "Res-0402-1K-5%"))
    )
    (comp (ref "R50")
      (value "1K")
      (footprint "RESC100X50X40L20N")
      (description "Resistor, 1K, 0.063W, 5%, 0402")
      (fields (field (name "Comment") "RC0402FR-071KL"))
      (libsource (lib "Resistors") (part "Res-0402-1K-5%"))
    )
    (comp (ref "R51")
      (value "1K")
      (footprint "RESC100X50X40L20N")
      (description "Resistor, 1K, 0.063W, 5%, 0402")
      (fields (field (name "Comment") "RC0402FR-071KL"))
      (libsource (lib "Resistors") (part "Res-0402-1K-5%"))
    )
    (comp (ref "R52")
      (value "1K")
      (footprint "RESC100X50X40L20N")
      (description "Resistor, 1K, 0.063W, 5%, 0402")
      (fields (field (name "Comment") "RC0402FR-071KL"))
      (libsource (lib "Resistors") (part "Res-0402-1K-5%"))
    )
    (comp (ref "R97")
      (value "6.8K")
      (footprint "RESC100X50X40L20N")
      (description "Resistor, 6.8K, 0.063W, 1%, 0402")
      (fields (field (name "Comment") "RC0402FR-076K8L"))
      (libsource (lib "") (part "Res-0402-6.8K-1%_1"))
    )
    (comp (ref "R99")
      (value "6.8K")
      (footprint "RESC100X50X40L20N")
      (description "Resistor, 6.8K, 0.063W, 1%, 0402")
      (fields (field (name "Comment") "RC0402FR-076K8L"))
      (libsource (lib "") (part "Res-0402-6.8K-1%_1"))
    )
    (comp (ref "R125")
      (value "680")
      (footprint "RESC100X50X40L20N")
      (description "Resistor, 680, 0.063W, 5%, 0402")
      (fields (field (name "Comment") "RC0402FR-07680RL"))
      (libsource (lib "Resistors") (part "Res-0402-680-5%"))
    )
    (comp (ref "R126")
      (value "150")
      (footprint "RESC100X50X40L20N")
      (description "Resistor, 150, 0.063W, 5%, 0402")
      (fields (field (name "Comment") "RC0402FR-07150RL"))
      (libsource (lib "Resistors") (part "Res-0402-150-5%"))
    )
    (comp (ref "U1")
      (value "TCA6416ARTWR")
      (footprint "QFN25P50_400X400X80L40X24T250N")
      (description "IC, Expander, 16-bit, 400KHZ, I2C, SMBUS, 1.65-5.5V, -40/+85, 24-WQFN (4x4)")
      (fields (field (name "MANUFACTURER") "TI"))
      (libsource (lib "IC Digital") (part "TCA6416ARTWR"))
    )
    (comp (ref "U2")
      (value "TPS2121RUXR")
      (footprint "QFN12P50_250X200X100L40X20N")
      (description "IC, QR controller, 2:1, 2.8/24V, 1/4.5A, -40/+125, VQFN-12")
      (fields (field (name "MANUFACTURER") "Texas Instruments"))
      (libsource (lib "IC Power") (part "TPS2121RUXR"))
    )
    (comp (ref "U3")
      (value "TPS62130RGTR")
      (footprint "QFN17P50_300X300X100L40X24T170N")
      (description "IC, DC/DC, Step-Down, 3-17/0.9-6V, 3A, -40/+85, QFN-16")
      (fields (field (name "MANUFACTURER") "Texas Instruments"))
      (libsource (lib "IC Power") (part "TPS62130RGTR"))
    )
    (comp (ref "U4")
      (value "SN74LXC2T45DCUR")
      (footprint "SOP8P50_200X310X90L27X21N")
      (description "IC, Transceiver, Bidirectional, 1.1-5.5V, -40/+125, 8VSSOP")
      (fields (field (name "MANUFACTURER") "TI"))
      (libsource (lib "IC Digital") (part "SN74LXC2T45DCUR"))
    )
    (comp (ref "U5")
      (value "SN74LXC2T45DCUR")
      (footprint "SOP8P50_200X310X90L27X21N")
      (description "IC, Transceiver, Bidirectional, 1.1-5.5V, -40/+125, 8VSSOP")
      (fields (field (name "MANUFACTURER") "TI"))
      (libsource (lib "IC Digital") (part "SN74LXC2T45DCUR"))
    )
    (comp (ref "U6")
      (value "SN74LXC2T45DCUR")
      (footprint "SOP8P50_200X310X90L27X21N")
      (description "IC, Transceiver, Bidirectional, 1.1-5.5V, -40/+125, 8VSSOP")
      (fields (field (name "MANUFACTURER") "TI"))
      (libsource (lib "IC Digital") (part "SN74LXC2T45DCUR"))
    )
    (comp (ref "U7")
      (value "TLV76601QWDRBRQ1")
      (footprint "SON9P65_300X300X100L40X31T250X175N")
      (description "IC, VolReg, DC/DC, 2.5/16V, 0.8/14,6V, 0.5A, -40/+150, 8-SON")
      (fields (field (name "MANUFACTURER") "Texas Instruments"))
      (libsource (lib "IC Power") (part "TLV76601QWDRBRQ1"))
    )
    (comp (ref "U8")
      (value "TLV76601QWDRBRQ1")
      (footprint "SON9P65_300X300X100L40X31T250X175N")
      (description "IC, VolReg, DC/DC, 2.5/16V, 0.8/14,6V, 0.5A, -40/+150, 8-SON")
      (fields (field (name "MANUFACTURER") "Texas Instruments"))
      (libsource (lib "IC Power") (part "TLV76601QWDRBRQ1"))
    )
    (comp (ref "U9")
      (value "TLV76601QWDRBRQ1")
      (footprint "SON9P65_300X300X100L40X31T250X175N")
      (description "IC, VolReg, DC/DC, 2.5/16V, 0.8/14,6V, 0.5A, -40/+150, 8-SON")
      (fields (field (name "MANUFACTURER") "Texas Instruments"))
      (libsource (lib "IC Power") (part "TLV76601QWDRBRQ1"))
    )
    (comp (ref "U10")
      (value "TLV76601QWDRBRQ1")
      (footprint "SON9P65_300X300X100L40X31T250X175N")
      (description "IC, VolReg, DC/DC, 2.5/16V, 0.8/14,6V, 0.5A, -40/+150, 8-SON")
      (fields (field (name "MANUFACTURER") "Texas Instruments"))
      (libsource (lib "IC Power") (part "TLV76601QWDRBRQ1"))
    )
    (comp (ref "U11")
      (value "TPS62130RGTR")
      (footprint "QFN17P50_300X300X100L40X24T170N")
      (description "IC, DC/DC, Step-Down, 3-17/0.9-6V, 3A, -40/+85, QFN-16")
      (fields (field (name "MANUFACTURER") "Texas Instruments"))
      (libsource (lib "IC Power") (part "TPS62130RGTR"))
    )
    (comp (ref "U12")
      (value "SN74LXC2T45DCUR")
      (footprint "SOP8P50_200X310X90L27X21N")
      (description "IC, Transceiver, Bidirectional, 1.1-5.5V, -40/+125, 8VSSOP")
      (fields (field (name "MANUFACTURER") "TI"))
      (libsource (lib "IC Digital") (part "SN74LXC2T45DCUR"))
    )
    (comp (ref "U14")
      (value "TLV76601QWDRBRQ1")
      (footprint "SON9P65_300X300X100L40X31T250X175N")
      (description "IC, VolReg, DC/DC, 2.5/16V, 0.8/14,6V, 0.5A, -40/+150, 8-SON")
      (fields (field (name "MANUFACTURER") "Texas Instruments"))
      (libsource (lib "IC Power") (part "TLV76601QWDRBRQ1"))
    )
  )
  (nets
    (net (code "1") (name "/CFG_PCIE") (class "Default")
      (node (ref "R13") (pin "2") (pinfunction "2_2") (pintype "passive"))
      (node (ref "U7") (pin "5") (pinfunction "EN_5") (pintype "passive"))
    )
    (net (code "2") (name "/CFG_USB3") (class "Default")
      (node (ref "R14") (pin "2") (pinfunction "2_2") (pintype "passive"))
      (node (ref "U8") (pin "5") (pinfunction "EN_5") (pintype "passive"))
    )
    (net (code "3") (name "/EGPIO6") (class "Default")
      (node (ref "R40") (pin "2") (pinfunction "2_2") (pintype "passive"))
      (node (ref "U6") (pin "7") (pinfunction "B1_7") (pintype "passive"))
    )
    (net (code "4") (name "/EGPIO7") (class "Default")
      (node (ref "R39") (pin "2") (pinfunction "2_2") (pintype "passive"))
      (node (ref "U6") (pin "6") (pinfunction "B2_6") (pintype "passive"))
    )
    (net (code "5") (name "/EGPIO8") (class "Default")
      (node (ref "R38") (pin "2") (pinfunction "2_2") (pintype "passive"))
      (node (ref "U5") (pin "7") (pinfunction "B1_7") (pintype "passive"))
    )
    (net (code "6") (name "/EGPIO9") (class "Default")
      (node (ref "R37") (pin "2") (pinfunction "2_2") (pintype "passive"))
      (node (ref "U5") (pin "6") (pinfunction "B2_6") (pintype "passive"))
    )
    (net (code "7") (name "/EGPIO10") (class "Default")
      (node (ref "R36") (pin "2") (pinfunction "2_2") (pintype "passive"))
      (node (ref "U4") (pin "7") (pinfunction "B1_7") (pintype "passive"))
    )
    (net (code "8") (name "/EGPIO11") (class "Default")
      (node (ref "R35") (pin "2") (pinfunction "2_2") (pintype "passive"))
      (node (ref "U4") (pin "6") (pinfunction "B2_6") (pintype "passive"))
    )
    (net (code "9") (name "/EGPIO12") (class "Default")
      (node (ref "R42") (pin "2") (pinfunction "2_2") (pintype "passive"))
      (node (ref "U12") (pin "7") (pinfunction "B1_7") (pintype "passive"))
    )
    (net (code "10") (name "/EGPIO13") (class "Default")
      (node (ref "R41") (pin "2") (pinfunction "2_2") (pintype "passive"))
      (node (ref "U12") (pin "6") (pinfunction "B2_6") (pintype "passive"))
    )
    (net (code "11") (name "/EGPIO67_VCC") (class "Default")
      (node (ref "C13") (pin "2") (pinfunction "2_2") (pintype "passive"))
      (node (ref "J1") (pin "17") (pinfunction "17_17") (pintype "passive"))
      (node (ref "U6") (pin "8") (pinfunction "VCCB_8") (pintype "passive"))
    )
    (net (code "12") (name "/EGPIO89_VCC") (class "Default")
      (node (ref "C12") (pin "2") (pinfunction "2_2") (pintype "passive"))
      (node (ref "J1") (pin "21") (pinfunction "21_21") (pintype "passive"))
      (node (ref "U5") (pin "8") (pinfunction "VCCB_8") (pintype "passive"))
    )
    (net (code "13") (name "/EGPIOAB_VCC") (class "Default")
      (node (ref "C11") (pin "2") (pinfunction "2_2") (pintype "passive"))
      (node (ref "J1") (pin "25") (pinfunction "25_25") (pintype "passive"))
      (node (ref "U4") (pin "8") (pinfunction "VCCB_8") (pintype "passive"))
    )
    (net (code "14") (name "/EGPIOCD_VCC") (class "Default")
      (node (ref "C26") (pin "2") (pinfunction "2_2") (pintype "passive"))
      (node (ref "J1") (pin "13") (pinfunction "13_13") (pintype "passive"))
      (node (ref "U12") (pin "8") (pinfunction "VCCB_8") (pintype "passive"))
    )
    (net (code "15") (name "/EN_GPS") (class "Default")
      (node (ref "R97") (pin "2") (pinfunction "2_2") (pintype "passive"))
      (node (ref "U1") (pin "2") (pinfunction "P01_2") (pintype "passive"))
      (node (ref "U9") (pin "5") (pinfunction "EN_5") (pintype "passive"))
    )
    (net (code "16") (name "/EN_OSC") (class "Default")
      (node (ref "R99") (pin "2") (pinfunction "2_2") (pintype "passive"))
      (node (ref "U1") (pin "1") (pinfunction "P00_1") (pintype "passive"))
      (node (ref "U14") (pin "5") (pinfunction "EN_5") (pintype "passive"))
    )
    (net (code "21") (name "/GPIO6") (class "Default")
      (node (ref "U6") (pin "2") (pinfunction "A1_2") (pintype "passive"))
    )
    (net (code "22") (name "/GPIO7") (class "Default")
      (node (ref "U6") (pin "3") (pinfunction "A2_3") (pintype "passive"))
    )
    (net (code "23") (name "/GPIO8") (class "Default")
      (node (ref "U5") (pin "2") (pinfunction "A1_2") (pintype "passive"))
    )
    (net (code "24") (name "/GPIO9") (class "Default")
      (node (ref "U5") (pin "3") (pinfunction "A2_3") (pintype "passive"))
    )
    (net (code "25") (name "/GPIO10") (class "Default")
      (node (ref "U4") (pin "2") (pinfunction "A1_2") (pintype "passive"))
    )
    (net (code "26") (name "/GPIO11") (class "Default")
      (node (ref "U4") (pin "3") (pinfunction "A2_3") (pintype "passive"))
    )
    (net (code "27") (name "/GPIO14") (class "Default")
      (node (ref "U12") (pin "2") (pinfunction "A1_2") (pintype "passive"))
    )
    (net (code "28") (name "/GPIO15") (class "Default")
      (node (ref "U12") (pin "3") (pinfunction "A2_3") (pintype "passive"))
    )
    (net (code "29") (name "/GPIO67_DIR") (class "Default")
      (node (ref "U1") (pin "7") (pinfunction "P06_7") (pintype "passive"))
      (node (ref "U6") (pin "5") (pinfunction "DIR_5") (pintype "passive"))
    )
    (net (code "30") (name "/GPIO89_DIR") (class "Default")
      (node (ref "U1") (pin "6") (pinfunction "P05_6") (pintype "passive"))
      (node (ref "U5") (pin "5") (pinfunction "DIR_5") (pintype "passive"))
    )
    (net (code "31") (name "/GPIOAB_DIR") (class "Default")
      (node (ref "U1") (pin "5") (pinfunction "P04_5") (pintype "passive"))
      (node (ref "U4") (pin "5") (pinfunction "DIR_5") (pintype "passive"))
    )
    (net (code "32") (name "/GPIOCD_DIR") (class "Default")
      (node (ref "U1") (pin "8") (pinfunction "P07_8") (pintype "passive"))
      (node (ref "U12") (pin "5") (pinfunction "DIR_5") (pintype "passive"))
    )
    (net (code "33") (name "/GPIO_LED1#") (class "Default")
      (node (ref "Q5") (pin "1") (pinfunction "G_1") (pintype "passive"))
      (node (ref "U1") (pin "3") (pinfunction "P02_3") (pintype "passive"))
    )
    (net (code "34") (name "/GPIO_LED2#") (class "Default")
      (node (ref "Q4") (pin "1") (pinfunction "G_1") (pintype "passive"))
      (node (ref "U1") (pin "4") (pinfunction "P03_4") (pintype "passive"))
    )
    (net (code "35") (name "/GPIO_LED3#") (class "Default")
      (node (ref "Q3") (pin "1") (pinfunction "G_1") (pintype "passive"))
      (node (ref "U1") (pin "17") (pinfunction "P17_17") (pintype "passive"))
    )
    (net (code "36") (name "/GPIO_LED4#") (class "Default")
      (node (ref "Q2") (pin "1") (pinfunction "G_1") (pintype "passive"))
      (node (ref "U1") (pin "16") (pinfunction "P16_16") (pintype "passive"))
    )
    (net (code "37") (name "/I2C_INTR") (class "Default")
      (node (ref "U1") (pin "22") (pinfunction "~{INT}_22") (pintype "passive"))
    )
    (net (code "38") (name "/LS_GPIO0") (class "Default")
      (node (ref "R45") (pin "2") (pinfunction "2_2") (pintype "passive"))
      (node (ref "U1") (pin "10") (pinfunction "P10_10") (pintype "passive"))
    )
    (net (code "39") (name "/LS_GPIO1") (class "Default")
      (node (ref "R46") (pin "2") (pinfunction "2_2") (pintype "passive"))
      (node (ref "U1") (pin "11") (pinfunction "P11_11") (pintype "passive"))
    )
    (net (code "40") (name "/LS_GPIO2") (class "Default")
      (node (ref "R16") (pin "1") (pinfunction "1_1") (pintype "passive"))
      (node (ref "U1") (pin "12") (pinfunction "P12_12") (pintype "passive"))
    )
    (net (code "41") (name "/LS_GPIO3") (class "Default")
      (node (ref "R43") (pin "2") (pinfunction "2_2") (pintype "passive"))
      (node (ref "U1") (pin "13") (pinfunction "P13_13") (pintype "passive"))
    )
    (net (code "42") (name "/LS_GPIO4") (class "Default")
      (node (ref "R44") (pin "2") (pinfunction "2_2") (pintype "passive"))
      (node (ref "U1") (pin "14") (pinfunction "P14_14") (pintype "passive"))
    )
    (net (code "43") (name "/LS_GPIO5") (class "Default")
      (node (ref "R15") (pin "1") (pinfunction "1_1") (pintype "passive"))
      (node (ref "U1") (pin "15") (pinfunction "P15_15") (pintype "passive"))
    )
    (net (code "44") (name "/PCI_PERST#") (class "Default")
      (node (ref "R7") (pin "1") (pinfunction "1_1") (pintype "passive"))
    )
    (net (code "45") (name "/PG_3V45") (class "Default")
      (node (ref "D3") (pin "A") (pinfunction "A_A") (pintype "passive"))
      (node (ref "R33") (pin "1") (pinfunction "1_1") (pintype "passive"))
      (node (ref "R7") (pin "2") (pinfunction "2_2") (pintype "passive"))
      (node (ref "U3") (pin "4") (pinfunction "PG_4") (pintype "passive"))
    )
    (net (code "46") (name "/SCL") (class "Default")
      (node (ref "U1") (pin "19") (pinfunction "SCL_19") (pintype "passive"))
    )
    (net (code "47") (name "/SDA") (class "Default")
      (node (ref "U1") (pin "20") (pinfunction "SDA_20") (pintype "passive"))
    )
    (net (code "48") (name "GND") (class "Default")
      (node (ref "C1") (pin "1") (pinfunction "1_1") (pintype "passive"))
      (node (ref "C10") (pin "2") (pinfunction "2_2") (pintype "passive"))
      (node (ref "C104") (pin "2") (pinfunction "2_2") (pintype "passive"))
      (node (ref "C105") (pin "2") (pinfunction "2_2") (pintype "passive"))
      (node (ref "C11") (pin "1") (pinfunction "1_1") (pintype "passive"))
      (node (ref "C12") (pin "1") (pinfunction "1_1") (pintype "passive"))
      (node (ref "C13") (pin "1") (pinfunction "1_1") (pintype "passive"))
      (node (ref "C14") (pin "2") (pinfunction "2_2") (pintype "passive"))
      (node (ref "C15") (pin "2") (pinfunction "2_2") (pintype "passive"))
      (node (ref "C16") (pin "2") (pinfunction "2_2") (pintype "passive"))
      (node (ref "C17") (pin "2") (pinfunction "2_2") (pintype "passive"))
      (node (ref "C18") (pin "2") (pinfunction "2_2") (pintype "passive"))
      (node (ref "C19") (pin "2") (pinfunction "2_2") (pintype "passive"))
      (node (ref "C2") (pin "1") (pinfunction "1_1") (pintype "passive"))
      (node (ref "C20") (pin "2") (pinfunction "2_2") (pintype "passive"))
      (node (ref "C21") (pin "2") (pinfunction "2_2") (pintype "passive"))
      (node (ref "C22") (pin "2") (pinfunction "2_2") (pintype "passive"))
      (node (ref "C23") (pin "2") (pinfunction "2_2") (pintype "passive"))
      (node (ref "C24") (pin "2") (pinfunction "2_2") (pintype "passive"))
      (node (ref "C25") (pin "2") (pinfunction "2_2") (pintype "passive"))
      (node (ref "C26") (pin "1") (pinfunction "1_1") (pintype "passive"))
      (node (ref "C27") (pin "2") (pinfunction "2_2") (pintype "passive"))
      (node (ref "C28") (pin "2") (pinfunction "2_2") (pintype "passive"))
      (node (ref "C29") (pin "2") (pinfunction "2_2") (pintype "passive"))
      (node (ref "C3") (pin "2") (pinfunction "2_2") (pintype "passive"))
      (node (ref "C4") (pin "2") (pinfunction "2_2") (pintype "passive"))
      (node (ref "C5") (pin "2") (pinfunction "2_2") (pintype "passive"))
      (node (ref "C6") (pin "2") (pinfunction "2_2") (pintype "passive"))
      (node (ref "C7") (pin "2") (pinfunction "2_2") (pintype "passive"))
      (node (ref "C8") (pin "2") (pinfunction "2_2") (pintype "passive"))
      (node (ref "C9") (pin "2") (pinfunction "2_2") (pintype "passive"))
      (node (ref "D1") (pin "C") (pinfunction "C_C") (pintype "passive"))
      (node (ref "D2") (pin "C") (pinfunction "C_C") (pintype "passive"))
      (node (ref "D3") (pin "C") (pinfunction "C_C") (pintype "passive"))
      (node (ref "J1") (pin "11") (pinfunction "11_11") (pintype "passive"))
      (node (ref "J1") (pin "15") (pinfunction "15_15") (pintype "passive"))
      (node (ref "J1") (pin "19") (pinfunction "19_19") (pintype "passive"))
      (node (ref "J1") (pin "23") (pinfunction "23_23") (pintype "passive"))
      (node (ref "J1") (pin "3") (pinfunction "3_3") (pintype "passive"))
      (node (ref "J1") (pin "7") (pinfunction "7_7") (pintype "passive"))
      (node (ref "Q1") (pin "2") (pinfunction "S_2") (pintype "passive"))
      (node (ref "Q2") (pin "2") (pinfunction "S_2") (pintype "passive"))
      (node (ref "Q3") (pin "2") (pinfunction "S_2") (pintype "passive"))
      (node (ref "Q4") (pin "2") (pinfunction "S_2") (pintype "passive"))
      (node (ref "Q5") (pin "2") (pinfunction "S_2") (pintype "passive"))
      (node (ref "R1") (pin "1") (pinfunction "1_1") (pintype "passive"))
      (node (ref "R10") (pin "2") (pinfunction "2_2") (pintype "passive"))
      (node (ref "R11") (pin "1") (pinfunction "1_1") (pintype "passive"))
      (node (ref "R125") (pin "1") (pinfunction "1_1") (pintype "passive"))
      (node (ref "R13") (pin "1") (pinfunction "1_1") (pintype "passive"))
      (node (ref "R14") (pin "1") (pinfunction "1_1") (pintype "passive"))
      (node (ref "R17") (pin "1") (pinfunction "1_1") (pintype "passive"))
      (node (ref "R23") (pin "1") (pinfunction "1_1") (pintype "passive"))
      (node (ref "R25") (pin "1") (pinfunction "1_1") (pintype "passive"))
      (node (ref "R27") (pin "1") (pinfunction "1_1") (pintype "passive"))
      (node (ref "R29") (pin "1") (pinfunction "1_1") (pintype "passive"))
      (node (ref "R4") (pin "1") (pinfunction "1_1") (pintype "passive"))
      (node (ref "R47") (pin "1") (pinfunction "1_1") (pintype "passive"))
      (node (ref "R5") (pin "1") (pinfunction "1_1") (pintype "passive"))
      (node (ref "R6") (pin "1") (pinfunction "1_1") (pintype "passive"))
      (node (ref "R8") (pin "1") (pinfunction "1_1") (pintype "passive"))
      (node (ref "R9") (pin "2") (pinfunction "2_2") (pintype "passive"))
      (node (ref "R97") (pin "1") (pinfunction "1_1") (pintype "passive"))
      (node (ref "R99") (pin "1") (pinfunction "1_1") (pintype "passive"))
      (node (ref "U1") (pin "9") (pinfunction "GND_9") (pintype "passive"))
      (node (ref "U1") (pin "EP") (pinfunction "EP_EP") (pintype "passive"))
      (node (ref "U10") (pin "4") (pinfunction "GND_4") (pintype "passive"))
      (node (ref "U10") (pin "6") (pinfunction "GND_6") (pintype "passive"))
      (node (ref "U10") (pin "EP") (pinfunction "GND_EP") (pintype "passive"))
      (node (ref "U11") (pin "15") (pinfunction "PGND_15") (pintype "passive"))
      (node (ref "U11") (pin "16") (pinfunction "PGND_16") (pintype "passive"))
      (node (ref "U11") (pin "6") (pinfunction "AGND_6") (pintype "passive"))
      (node (ref "U11") (pin "7") (pinfunction "FSW_7") (pintype "passive"))
      (node (ref "U11") (pin "8") (pinfunction "DEF_8") (pintype "passive"))
      (node (ref "U11") (pin "EP") (pinfunction "EP_EP") (pintype "passive"))
      (node (ref "U12") (pin "4") (pinfunction "GND_4") (pintype "passive"))
      (node (ref "U14") (pin "4") (pinfunction "GND_4") (pintype "passive"))
      (node (ref "U14") (pin "6") (pinfunction "GND_6") (pintype "passive"))
      (node (ref "U14") (pin "EP") (pinfunction "GND_EP") (pintype "passive"))
      (node (ref "U2") (pin "12") (pinfunction "GND_12") (pintype "power_in"))
      (node (ref "U3") (pin "15") (pinfunction "PGND_15") (pintype "passive"))
      (node (ref "U3") (pin "16") (pinfunction "PGND_16") (pintype "passive"))
      (node (ref "U3") (pin "6") (pinfunction "AGND_6") (pintype "passive"))
      (node (ref "U3") (pin "7") (pinfunction "FSW_7") (pintype "passive"))
      (node (ref "U3") (pin "8") (pinfunction "DEF_8") (pintype "passive"))
      (node (ref "U3") (pin "EP") (pinfunction "EP_EP") (pintype "passive"))
      (node (ref "U4") (pin "4") (pinfunction "GND_4") (pintype "passive"))
      (node (ref "U5") (pin "4") (pinfunction "GND_4") (pintype "passive"))
      (node (ref "U6") (pin "4") (pinfunction "GND_4") (pintype "passive"))
      (node (ref "U7") (pin "4") (pinfunction "GND_4") (pintype "passive"))
      (node (ref "U7") (pin "6") (pinfunction "GND_6") (pintype "passive"))
      (node (ref "U7") (pin "EP") (pinfunction "GND_EP") (pintype "passive"))
      (node (ref "U8") (pin "4") (pinfunction "GND_4") (pintype "passive"))
      (node (ref "U8") (pin "6") (pinfunction "GND_6") (pintype "passive"))
      (node (ref "U8") (pin "EP") (pinfunction "GND_EP") (pintype "passive"))
      (node (ref "U9") (pin "4") (pinfunction "GND_4") (pintype "passive"))
      (node (ref "U9") (pin "6") (pinfunction "GND_6") (pintype "passive"))
      (node (ref "U9") (pin "EP") (pinfunction "GND_EP") (pintype "passive"))
    )
    (net (code "49") (name "Net-(C104-Pad1)") (class "Default")
      (node (ref "C104") (pin "1") (pinfunction "1_1") (pintype "passive"))
      (node (ref "L57") (pin "2") (pinfunction "2_2") (pintype "passive"))
      (node (ref "R126") (pin "2") (pinfunction "2_2") (pintype "passive"))
    )
    (net (code "50") (name "Net-(D1-PadA)") (class "Default")
      (node (ref "D1") (pin "A") (pinfunction "A_A") (pintype "passive"))
      (node (ref "R31") (pin "1") (pinfunction "1_1") (pintype "passive"))
    )
    (net (code "51") (name "Net-(D2-PadA)") (class "Default")
      (node (ref "D2") (pin "A") (pinfunction "A_A") (pintype "passive"))
      (node (ref "R32") (pin "1") (pinfunction "1_1") (pintype "passive"))
    )
    (net (code "52") (name "Net-(D4-PadA)") (class "Default")
      (node (ref "D4") (pin "A") (pinfunction "A_A") (pintype "passive"))
      (node (ref "R34") (pin "1") (pinfunction "1_1") (pintype "passive"))
    )
    (net (code "53") (name "Net-(D5-PadA)") (class "Default")
      (node (ref "D5") (pin "A") (pinfunction "A_A") (pintype "passive"))
      (node (ref "R49") (pin "1") (pinfunction "1_1") (pintype "passive"))
    )
    (net (code "54") (name "Net-(D6-PadA)") (class "Default")
      (node (ref "D6") (pin "A") (pinfunction "A_A") (pintype "passive"))
      (node (ref "R50") (pin "1") (pinfunction "1_1") (pintype "passive"))
    )
    (net (code "55") (name "Net-(D7-PadA)") (class "Default")
      (node (ref "D7") (pin "A") (pinfunction "A_A") (pintype "passive"))
      (node (ref "R51") (pin "1") (pinfunction "1_1") (pintype "passive"))
    )
    (net (code "56") (name "Net-(D8-PadA)") (class "Default")
      (node (ref "D8") (pin "A") (pinfunction "A_A") (pintype "passive"))
      (node (ref "R52") (pin "1") (pinfunction "1_1") (pintype "passive"))
    )
    (net (code "57") (name "Net-(J1-Pad4)") (class "Default")
      (node (ref "J1") (pin "4") (pinfunction "4_4") (pintype "passive"))
      (node (ref "R45") (pin "1") (pinfunction "1_1") (pintype "passive"))
    )
    (net (code "58") (name "Net-(J1-Pad5)") (class "Default")
      (node (ref "J1") (pin "5") (pinfunction "5_5") (pintype "passive"))
      (node (ref "R16") (pin "2") (pinfunction "2_2") (pintype "passive"))
    )
    (net (code "59") (name "Net-(J1-Pad6)") (class "Default")
      (node (ref "J1") (pin "6") (pinfunction "6_6") (pintype "passive"))
      (node (ref "R46") (pin "1") (pinfunction "1_1") (pintype "passive"))
    )
    (net (code "60") (name "Net-(J1-Pad8)") (class "Default")
      (node (ref "J1") (pin "8") (pinfunction "8_8") (pintype "passive"))
      (node (ref "R43") (pin "1") (pinfunction "1_1") (pintype "passive"))
    )
    (net (code "61") (name "Net-(J1-Pad9)") (class "Default")
      (node (ref "J1") (pin "9") (pinfunction "9_9") (pintype "passive"))
      (node (ref "R15") (pin "2") (pinfunction "2_2") (pintype "passive"))
    )
    (net (code "62") (name "Net-(J1-Pad10)") (class "Default")
      (node (ref "J1") (pin "10") (pinfunction "10_10") (pintype "passive"))
      (node (ref "R44") (pin "1") (pinfunction "1_1") (pintype "passive"))
    )
    (net (code "63") (name "Net-(J1-Pad12)") (class "Default")
      (node (ref "J1") (pin "12") (pinfunction "12_12") (pintype "passive"))
      (node (ref "R41") (pin "1") (pinfunction "1_1") (pintype "passive"))
    )
    (net (code "64") (name "Net-(J1-Pad14)") (class "Default")
      (node (ref "J1") (pin "14") (pinfunction "14_14") (pintype "passive"))
      (node (ref "R42") (pin "1") (pinfunction "1_1") (pintype "passive"))
    )
    (net (code "65") (name "Net-(J1-Pad16)") (class "Default")
      (node (ref "J1") (pin "16") (pinfunction "16_16") (pintype "passive"))
      (node (ref "R39") (pin "1") (pinfunction "1_1") (pintype "passive"))
    )
    (net (code "66") (name "Net-(J1-Pad18)") (class "Default")
      (node (ref "J1") (pin "18") (pinfunction "18_18") (pintype "passive"))
      (node (ref "R40") (pin "1") (pinfunction "1_1") (pintype "passive"))
    )
    (net (code "67") (name "Net-(J1-Pad20)") (class "Default")
      (node (ref "J1") (pin "20") (pinfunction "20_20") (pintype "passive"))
      (node (ref "R37") (pin "1") (pinfunction "1_1") (pintype "passive"))
    )
    (net (code "68") (name "Net-(J1-Pad22)") (class "Default")
      (node (ref "J1") (pin "22") (pinfunction "22_22") (pintype "passive"))
      (node (ref "R38") (pin "1") (pinfunction "1_1") (pintype "passive"))
    )
    (net (code "69") (name "Net-(J1-Pad24)") (class "Default")
      (node (ref "J1") (pin "24") (pinfunction "24_24") (pintype "passive"))
      (node (ref "R35") (pin "1") (pinfunction "1_1") (pintype "passive"))
    )
    (net (code "70") (name "Net-(J1-Pad26)") (class "Default")
      (node (ref "J1") (pin "26") (pinfunction "26_26") (pintype "passive"))
      (node (ref "R36") (pin "1") (pinfunction "1_1") (pintype "passive"))
    )
    (net (code "71") (name "Net-(L1-Pad1)") (class "Default")
      (node (ref "L1") (pin "1") (pinfunction "1_1") (pintype "passive"))
      (node (ref "U3") (pin "1") (pinfunction "SW_1") (pintype "passive"))
      (node (ref "U3") (pin "2") (pinfunction "SW_2") (pintype "passive"))
      (node (ref "U3") (pin "3") (pinfunction "SW_3") (pintype "passive"))
    )
    (net (code "72") (name "Net-(L21-Pad1)") (class "Default")
      (node (ref "L21") (pin "1") (pinfunction "1_1") (pintype "passive"))
      (node (ref "U11") (pin "1") (pinfunction "SW_1") (pintype "passive"))
      (node (ref "U11") (pin "2") (pinfunction "SW_2") (pintype "passive"))
      (node (ref "U11") (pin "3") (pinfunction "SW_3") (pintype "passive"))
    )
    (net (code "73") (name "Net-(Q1-D)") (class "Default")
      (node (ref "D4") (pin "C") (pinfunction "C_C") (pintype "passive"))
      (node (ref "Q1") (pin "3") (pinfunction "D_3") (pintype "passive"))
    )
    (net (code "74") (name "Net-(Q2-D)") (class "Default")
      (node (ref "D5") (pin "C") (pinfunction "C_C") (pintype "passive"))
      (node (ref "Q2") (pin "3") (pinfunction "D_3") (pintype "passive"))
    )
    (net (code "75") (name "Net-(Q3-D)") (class "Default")
      (node (ref "D6") (pin "C") (pinfunction "C_C") (pintype "passive"))
      (node (ref "Q3") (pin "3") (pinfunction "D_3") (pintype "passive"))
    )
    (net (code "76") (name "Net-(Q4-D)") (class "Default")
      (node (ref "D7") (pin "C") (pinfunction "C_C") (pintype "passive"))
      (node (ref "Q4") (pin "3") (pinfunction "D_3") (pintype "passive"))
    )
    (net (code "77") (name "Net-(Q5-D)") (class "Default")
      (node (ref "D8") (pin "C") (pinfunction "C_C") (pintype "passive"))
      (node (ref "Q5") (pin "3") (pinfunction "D_3") (pintype "passive"))
    )
    (net (code "78") (name "Net-(U1-ADDR)") (class "Default")
      (node (ref "R1") (pin "2") (pinfunction "2_2") (pintype "passive"))
      (node (ref "R2") (pin "2") (pinfunction "2_2") (pintype "passive"))
      (node (ref "U1") (pin "18") (pinfunction "ADDR_18") (pintype "passive"))
    )
    (net (code "79") (name "Net-(U1-~{RESET})") (class "Default")
      (node (ref "R3") (pin "2") (pinfunction "2_2") (pintype "passive"))
      (node (ref "U1") (pin "24") (pinfunction "~{RESET}_24") (pintype "passive"))
    )
    (net (code "80") (name "Net-(U2-CP2)") (class "Default")
      (node (ref "R9") (pin "1") (pinfunction "1_1") (pintype "passive"))
      (node (ref "U2") (pin "3") (pinfunction "CP2_3") (pintype "passive"))
    )
    (net (code "81") (name "Net-(U2-ILM)") (class "Default")
      (node (ref "R8") (pin "2") (pinfunction "2_2") (pintype "passive"))
      (node (ref "U2") (pin "10") (pinfunction "ILM_10") (pintype "passive"))
    )
    (net (code "82") (name "Net-(U2-OV1)") (class "Default")
      (node (ref "R6") (pin "2") (pinfunction "2_2") (pintype "passive"))
      (node (ref "U2") (pin "5") (pinfunction "OV1_5") (pintype "passive"))
    )
    (net (code "83") (name "Net-(U2-OV2)") (class "Default")
      (node (ref "R4") (pin "2") (pinfunction "2_2") (pintype "passive"))
      (node (ref "U2") (pin "4") (pinfunction "OV2_4") (pintype "passive"))
    )
    (net (code "84") (name "Net-(U2-PR1)") (class "Default")
      (node (ref "R5") (pin "2") (pinfunction "2_2") (pintype "passive"))
      (node (ref "U2") (pin "6") (pinfunction "PR1_6") (pintype "passive"))
    )
    (net (code "85") (name "Net-(U2-SS)") (class "Default")
      (node (ref "C6") (pin "1") (pinfunction "1_1") (pintype "passive"))
      (node (ref "U2") (pin "11") (pinfunction "SS_11") (pintype "passive"))
    )
    (net (code "86") (name "Net-(U2-ST)") (class "Default")
      (node (ref "R10") (pin "1") (pinfunction "1_1") (pintype "passive"))
      (node (ref "U2") (pin "9") (pinfunction "ST_9") (pintype "passive"))
    )
    (net (code "87") (name "Net-(U3-FB)") (class "Default")
      (node (ref "R11") (pin "2") (pinfunction "2_2") (pintype "passive"))
      (node (ref "R12") (pin "1") (pinfunction "1_1") (pintype "passive"))
      (node (ref "U3") (pin "5") (pinfunction "FB_5") (pintype "passive"))
    )
    (net (code "88") (name "Net-(U3-SS{slash}TR)") (class "Default")
      (node (ref "C4") (pin "1") (pinfunction "1_1") (pintype "passive"))
      (node (ref "U3") (pin "9") (pinfunction "SS/TR_9") (pintype "passive"))
    )
    (net (code "89") (name "Net-(U7-FB)") (class "Default")
      (node (ref "R27") (pin "2") (pinfunction "2_2") (pintype "passive"))
      (node (ref "R28") (pin "1") (pinfunction "1_1") (pintype "passive"))
      (node (ref "U7") (pin "3") (pinfunction "FB_3") (pintype "passive"))
    )
    (net (code "90") (name "Net-(U7-IN)") (class "Default")
      (node (ref "C14") (pin "1") (pinfunction "1_1") (pintype "passive"))
      (node (ref "D14") (pin "C") (pinfunction "C_C") (pintype "passive"))
      (node (ref "U7") (pin "8") (pinfunction "IN_8") (pintype "passive"))
    )
    (net (code "91") (name "Net-(U8-FB)") (class "Default")
      (node (ref "R29") (pin "2") (pinfunction "2_2") (pintype "passive"))
      (node (ref "R30") (pin "1") (pinfunction "1_1") (pintype "passive"))
      (node (ref "U8") (pin "3") (pinfunction "FB_3") (pintype "passive"))
    )
    (net (code "92") (name "Net-(U8-IN)") (class "Default")
      (node (ref "C15") (pin "1") (pinfunction "1_1") (pintype "passive"))
      (node (ref "L3") (pin "2") (pinfunction "2_2") (pintype "passive"))
      (node (ref "U8") (pin "8") (pinfunction "IN_8") (pintype "passive"))
    )
    (net (code "93") (name "Net-(U9-FB)") (class "Default")
      (node (ref "R23") (pin "2") (pinfunction "2_2") (pintype "passive"))
      (node (ref "R24") (pin "1") (pinfunction "1_1") (pintype "passive"))
      (node (ref "U9") (pin "3") (pinfunction "FB_3") (pintype "passive"))
    )
    (net (code "94") (name "Net-(U9-IN)") (class "Default")
      (node (ref "C16") (pin "1") (pinfunction "1_1") (pintype "passive"))
      (node (ref "L4") (pin "2") (pinfunction "2_2") (pintype "passive"))
      (node (ref "U9") (pin "8") (pinfunction "IN_8") (pintype "passive"))
    )
    (net (code "95") (name "Net-(U10-EN)") (class "Default")
      (node (ref "C17") (pin "1") (pinfunction "1_1") (pintype "passive"))
      (node (ref "L5") (pin "2") (pinfunction "2_2") (pintype "passive"))
      (node (ref "U10") (pin "5") (pinfunction "EN_5") (pintype "passive"))
      (node (ref "U10") (pin "8") (pinfunction "IN_8") (pintype "passive"))
    )
    (net (code "96") (name "Net-(U10-FB)") (class "Default")
      (node (ref "R25") (pin "2") (pinfunction "2_2") (pintype "passive"))
      (node (ref "R26") (pin "1") (pinfunction "1_1") (pintype "passive"))
      (node (ref "U10") (pin "3") (pinfunction "FB_3") (pintype "passive"))
    )
    (net (code "97") (name "Net-(U11-FB)") (class "Default")
      (node (ref "R17") (pin "2") (pinfunction "2_2") (pintype "passive"))
      (node (ref "R18") (pin "1") (pinfunction "1_1") (pintype "passive"))
      (node (ref "U11") (pin "5") (pinfunction "FB_5") (pintype "passive"))
    )
    (net (code "98") (name "Net-(U11-SS{slash}TR)") (class "Default")
      (node (ref "C20") (pin "1") (pinfunction "1_1") (pintype "passive"))
      (node (ref "U11") (pin "9") (pinfunction "SS/TR_9") (pintype "passive"))
    )
    (net (code "99") (name "Net-(U14-FB)") (class "Default")
      (node (ref "R47") (pin "2") (pinfunction "2_2") (pintype "passive"))
      (node (ref "R48") (pin "1") (pinfunction "1_1") (pintype "passive"))
      (node (ref "U14") (pin "3") (pinfunction "FB_3") (pintype "passive"))
    )
    (net (code "100") (name "Net-(U14-IN)") (class "Default")
      (node (ref "C28") (pin "1") (pinfunction "1_1") (pintype "passive"))
      (node (ref "L6") (pin "2") (pinfunction "2_2") (pintype "passive"))
      (node (ref "U14") (pin "8") (pinfunction "IN_8") (pintype "passive"))
    )
    (net (code "101") (name "VCC5P0") (class "Default")
      (node (ref "C23") (pin "1") (pinfunction "1_1") (pintype "passive"))
      (node (ref "C24") (pin "1") (pinfunction "1_1") (pintype "passive"))
      (node (ref "R28") (pin "2") (pinfunction "2_2") (pintype "passive"))
      (node (ref "R30") (pin "2") (pinfunction "2_2") (pintype "passive"))
      (node (ref "U7") (pin "1") (pinfunction "OUT_1") (pintype "passive"))
      (node (ref "U8") (pin "1") (pinfunction "OUT_1") (pintype "passive"))
    )
    (net (code "102") (name "VCC_1P8") (class "Default")
      (node (ref "C1") (pin "2") (pinfunction "2_2") (pintype "passive"))
      (node (ref "C10") (pin "1") (pinfunction "1_1") (pintype "passive"))
      (node (ref "C19") (pin "1") (pinfunction "1_1") (pintype "passive"))
      (node (ref "C2") (pin "2") (pinfunction "2_2") (pintype "passive"))
      (node (ref "C22") (pin "1") (pinfunction "1_1") (pintype "passive"))
      (node (ref "C8") (pin "1") (pinfunction "1_1") (pintype "passive"))
      (node (ref "C9") (pin "1") (pinfunction "1_1") (pintype "passive"))
      (node (ref "J1") (pin "27") (pinfunction "27_27") (pintype "passive"))
      (node (ref "J1") (pin "28") (pinfunction "28_28") (pintype "passive"))
      (node (ref "Q1") (pin "1") (pinfunction "G_1") (pintype "passive"))
      (node (ref "R2") (pin "1") (pinfunction "1_1") (pintype "passive"))
      (node (ref "R26") (pin "2") (pinfunction "2_2") (pintype "passive"))
      (node (ref "R3") (pin "1") (pinfunction "1_1") (pintype "passive"))
      (node (ref "U1") (pin "21") (pinfunction "VCCP_21") (pintype "passive"))
      (node (ref "U1") (pin "23") (pinfunction "VCCI_23") (pintype "passive"))
      (node (ref "U10") (pin "1") (pinfunction "OUT_1") (pintype "passive"))
      (node (ref "U12") (pin "1") (pinfunction "VCCA_1") (pintype "passive"))
      (node (ref "U4") (pin "1") (pinfunction "VCCA_1") (pintype "passive"))
      (node (ref "U5") (pin "1") (pinfunction "VCCA_1") (pintype "passive"))
      (node (ref "U6") (pin "1") (pinfunction "VCCA_1") (pintype "passive"))
    )
    (net (code "103") (name "VCC_3P45") (class "Default")
      (node (ref "C7") (pin "1") (pinfunction "1_1") (pintype "passive"))
      (node (ref "J1") (pin "1") (pinfunction "1_1") (pintype "passive"))
      (node (ref "J1") (pin "2") (pinfunction "2_2") (pintype "passive"))
      (node (ref "L1") (pin "2") (pinfunction "2_2") (pintype "passive"))
      (node (ref "L4") (pin "1") (pinfunction "1_1") (pintype "passive"))
      (node (ref "L5") (pin "1") (pinfunction "1_1") (pintype "passive"))
      (node (ref "L57") (pin "1") (pinfunction "1_1") (pintype "passive"))
      (node (ref "L6") (pin "1") (pinfunction "1_1") (pintype "passive"))
      (node (ref "R12") (pin "2") (pinfunction "2_2") (pintype "passive"))
      (node (ref "R33") (pin "2") (pinfunction "2_2") (pintype "passive"))
      (node (ref "R34") (pin "2") (pinfunction "2_2") (pintype "passive"))
      (node (ref "R49") (pin "2") (pinfunction "2_2") (pintype "passive"))
      (node (ref "R50") (pin "2") (pinfunction "2_2") (pintype "passive"))
      (node (ref "R51") (pin "2") (pinfunction "2_2") (pintype "passive"))
      (node (ref "R52") (pin "2") (pinfunction "2_2") (pintype "passive"))
      (node (ref "U3") (pin "14") (pinfunction "VOS_14") (pintype "passive"))
    )
    (net (code "104") (name "VCC_6P2") (class "Default")
      (node (ref "C27") (pin "1") (pinfunction "1_1") (pintype "passive"))
      (node (ref "D14") (pin "A") (pinfunction "A_A") (pintype "passive"))
      (node (ref "L21") (pin "2") (pinfunction "2_2") (pintype "passive"))
      (node (ref "R18") (pin "2") (pinfunction "2_2") (pintype "passive"))
      (node (ref "U11") (pin "14") (pinfunction "VOS_14") (pintype "passive"))
    )
    (net (code "105") (name "VCC_GPS_3P0") (class "Default")
      (node (ref "C21") (pin "1") (pinfunction "1_1") (pintype "passive"))
      (node (ref "R24") (pin "2") (pinfunction "2_2") (pintype "passive"))
      (node (ref "R32") (pin "2") (pinfunction "2_2") (pintype "passive"))
      (node (ref "U9") (pin "1") (pinfunction "OUT_1") (pintype "passive"))
    )
    (net (code "106") (name "VCC_MUX") (class "Default")
      (node (ref "C3") (pin "1") (pinfunction "1_1") (pintype "passive"))
      (node (ref "C5") (pin "1") (pinfunction "1_1") (pintype "passive"))
      (node (ref "L3") (pin "1") (pinfunction "1_1") (pintype "passive"))
      (node (ref "U2") (pin "1") (pinfunction "OUT_1") (pintype "passive"))
      (node (ref "U2") (pin "8") (pinfunction "OUT_8") (pintype "passive"))
      (node (ref "U3") (pin "10") (pinfunction "AVIN_10") (pintype "passive"))
      (node (ref "U3") (pin "11") (pinfunction "PVIN_11") (pintype "passive"))
      (node (ref "U3") (pin "12") (pinfunction "PVIN_12") (pintype "passive"))
      (node (ref "U3") (pin "13") (pinfunction "EN_13") (pintype "passive"))
    )
    (net (code "107") (name "VCC_OSC_3P0") (class "Default")
      (node (ref "C29") (pin "1") (pinfunction "1_1") (pintype "passive"))
      (node (ref "R31") (pin "2") (pinfunction "2_2") (pintype "passive"))
      (node (ref "R48") (pin "2") (pinfunction "2_2") (pintype "passive"))
      (node (ref "U14") (pin "1") (pinfunction "OUT_1") (pintype "passive"))
    )
    (net (code "108") (name "VCC_RF_3P0") (class "Default")
      (node (ref "C105") (pin "1") (pinfunction "1_1") (pintype "passive"))
      (node (ref "R125") (pin "2") (pinfunction "2_2") (pintype "passive"))
      (node (ref "R126") (pin "1") (pinfunction "1_1") (pintype "passive"))
    )
    (net (code "109") (name "VCC_USB") (class "Default")
      (node (ref "U2") (pin "7") (pinfunction "IN1_7") (pintype "passive"))
    )
    (net (code "110") (name "VIN_12P0") (class "Default")
      (node (ref "C18") (pin "1") (pinfunction "1_1") (pintype "passive"))
      (node (ref "C25") (pin "1") (pinfunction "1_1") (pintype "passive"))
      (node (ref "U11") (pin "10") (pinfunction "AVIN_10") (pintype "passive"))
      (node (ref "U11") (pin "11") (pinfunction "PVIN_11") (pintype "passive"))
      (node (ref "U11") (pin "12") (pinfunction "PVIN_12") (pintype "passive"))
      (node (ref "U11") (pin "13") (pinfunction "EN_13") (pintype "passive"))
      (node (ref "U2") (pin "2") (pinfunction "IN2_2") (pintype "passive"))
    )
    (net (code "111") (name "unconnected-(U11-PG-Pad4)") (class "Default")
      (node (ref "U11") (pin "4") (pinfunction "PG_4") (pintype "passive+no_connect"))
    )
  )
)
